# MA3050.net
KiCad netlist of a schematic drawn in EasyEDA Pro
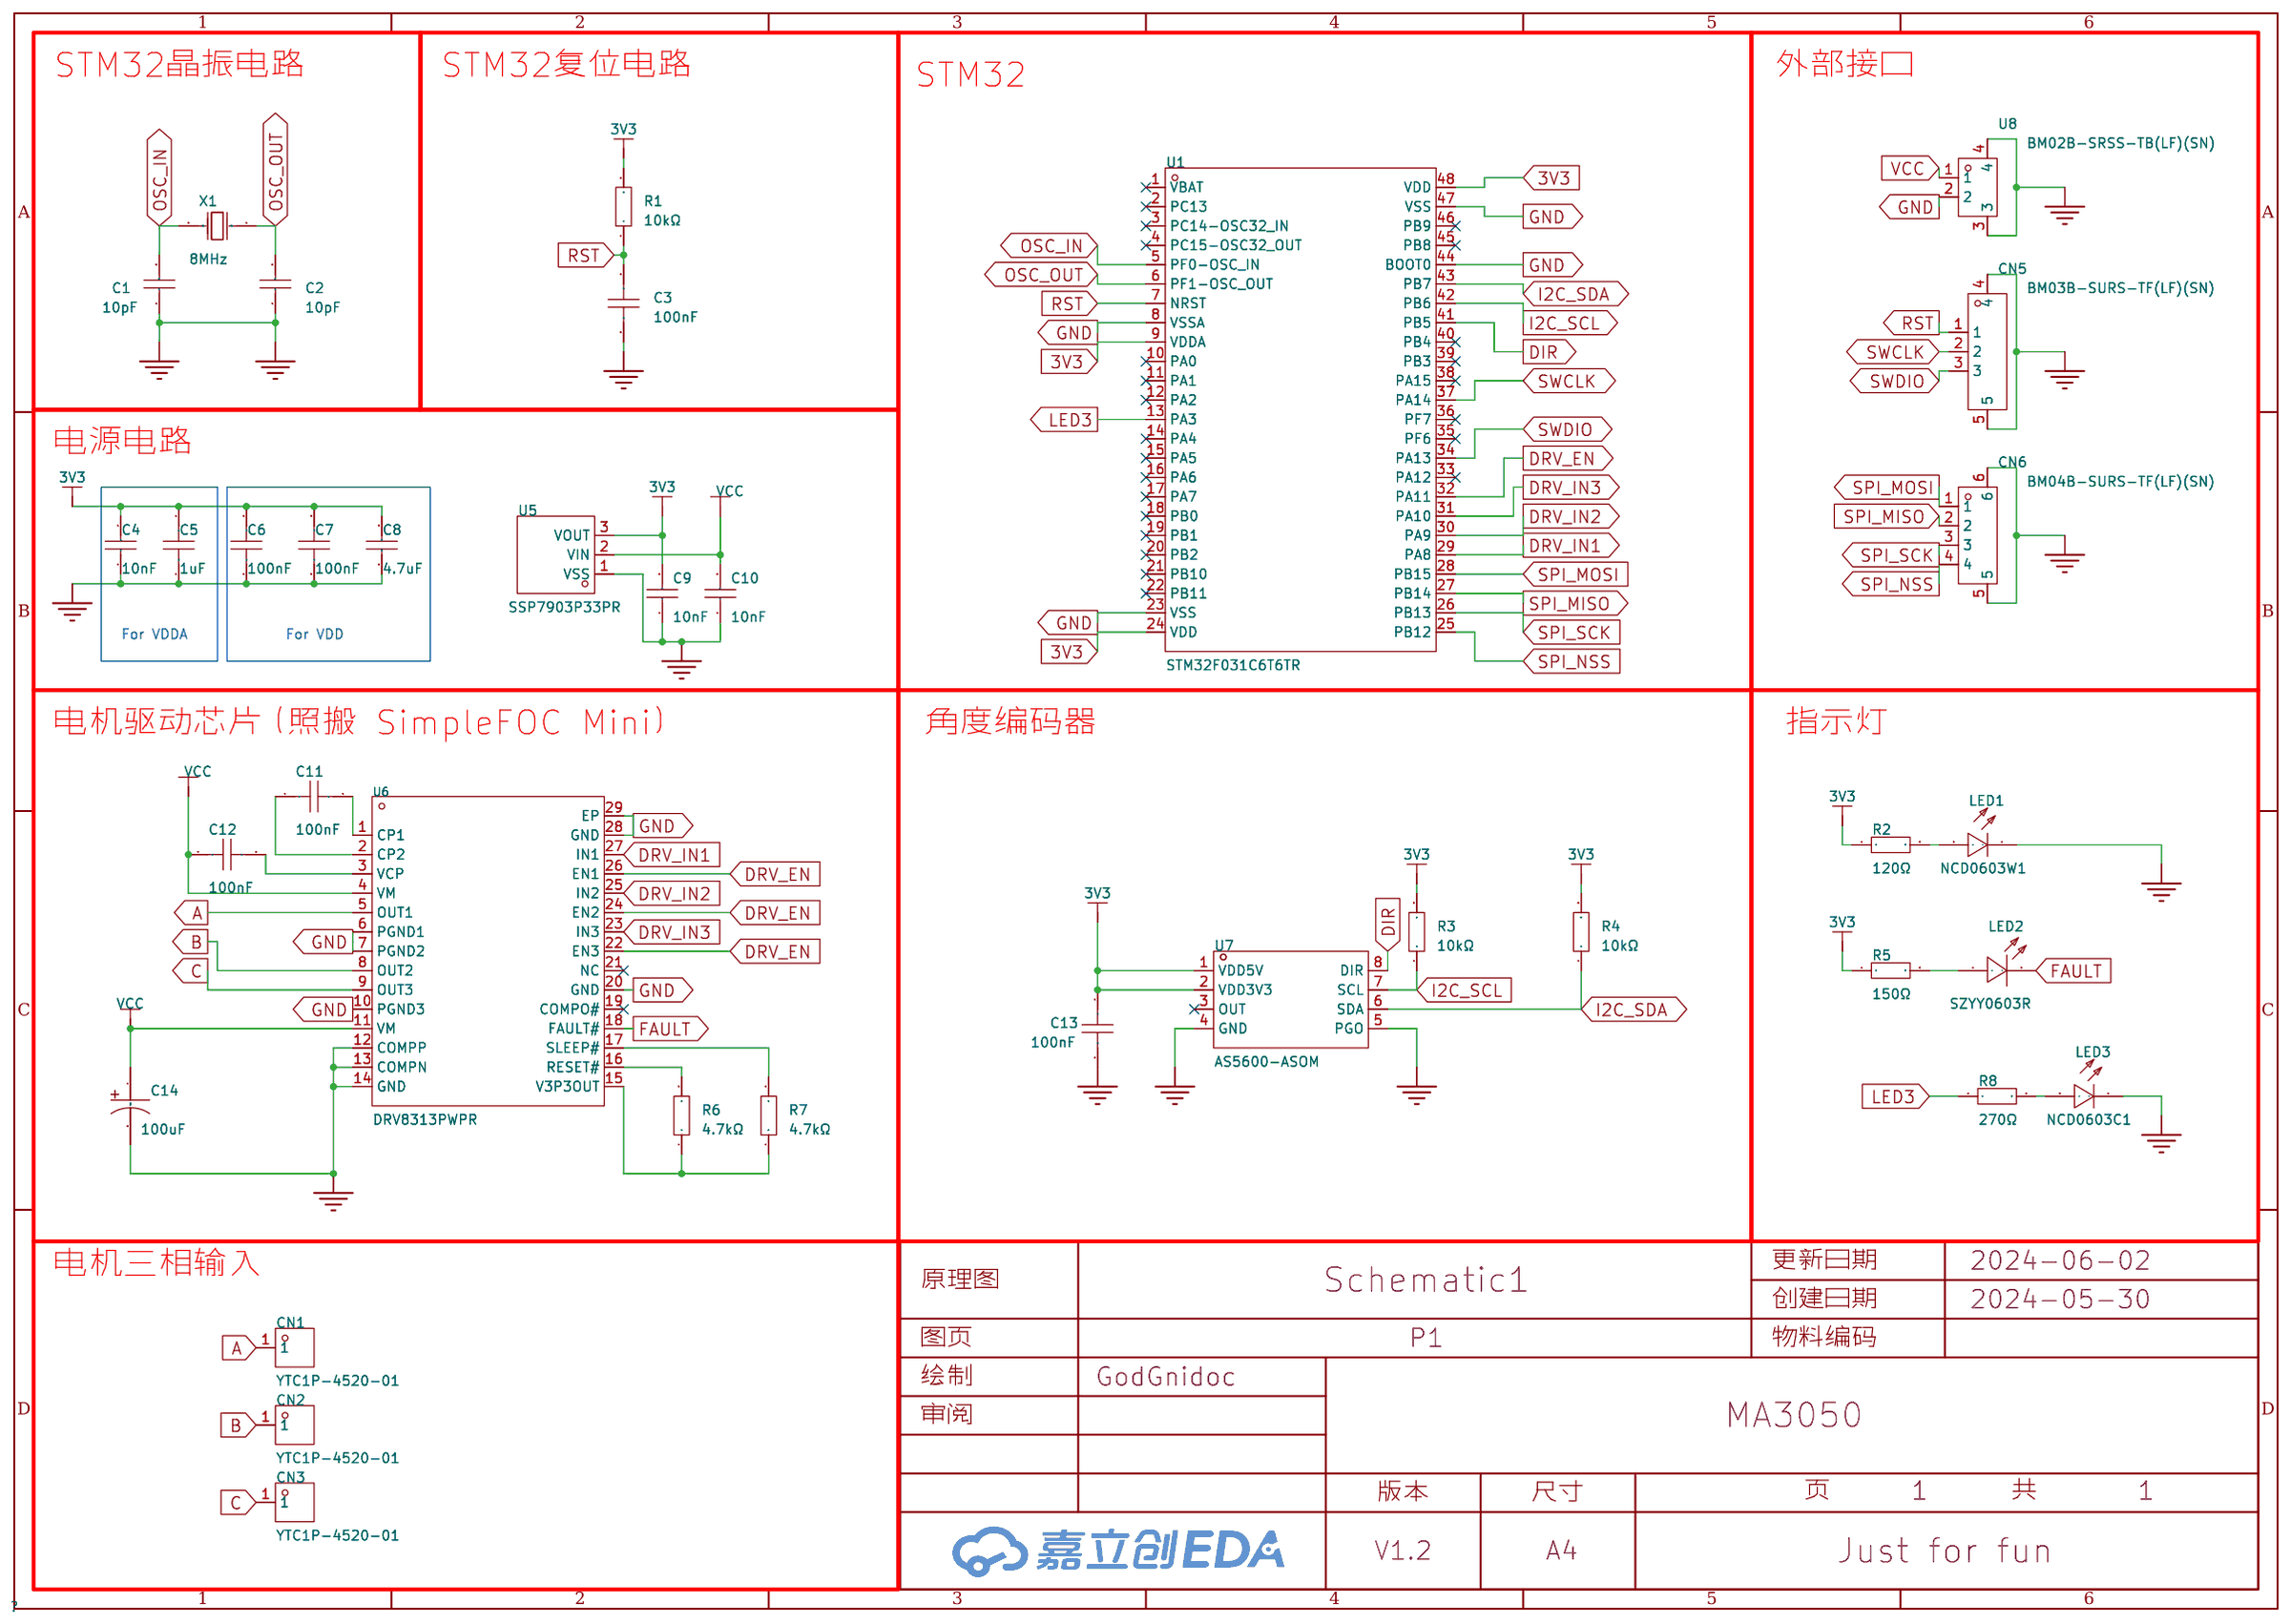
[diagram p0: schematic sheet]

(export (version "E")
  (design (tool "Eeschema 10.0.6"))
  (components
    (comp (ref "C1")
      (value "10pF")
      (footprint "easyedapro:C0603")
      (description "容值:10pF;精度:±5%;额定电压:50V;材质(温度系数):C0G;")
      (fields
        (field (name "Manufacturer Part") "CL10C100JB8NNNC")
        (field (name "Manufacturer") "SAMSUNG(三星)")
      )
      (libsource (lib "easyedapro") (part "CL10C100JB8NNNC"))
    )
    (comp (ref "C2")
      (value "10pF")
      (footprint "easyedapro:C0603")
      (description "容值:10pF;精度:±5%;额定电压:50V;材质(温度系数):C0G;")
      (fields
        (field (name "Manufacturer Part") "CL10C100JB8NNNC")
        (field (name "Manufacturer") "SAMSUNG(三星)")
      )
      (libsource (lib "easyedapro") (part "CL10C100JB8NNNC"))
    )
    (comp (ref "C3")
      (value "100nF")
      (footprint "easyedapro:C0603")
      (description "容值:100nF;精度:±10%;额定电压:50V;材质(温度系数):X7R;")
      (fields
        (field (name "Manufacturer Part") "CL10B104KB8NNNC")
        (field (name "Manufacturer") "SAMSUNG(三星)")
      )
      (libsource (lib "easyedapro") (part "CL10B104KB8NNNC"))
    )
    (comp (ref "C4")
      (value "10nF")
      (footprint "easyedapro:C0603")
      (description "容值:10nF;精度:±10%;额定电压:50V;材质(温度系数):X7R;")
      (fields
        (field (name "Manufacturer Part") "CC0603KRX7R9BB103")
        (field (name "Manufacturer") "YAGEO(国巨)")
      )
      (libsource (lib "easyedapro") (part "CC0603KRX7R9BB103"))
    )
    (comp (ref "C5")
      (value "1uF")
      (footprint "easyedapro:C0603")
      (description "容值:1uF;精度:±10%;额定电压:50V;材质(温度系数):X5R;")
      (fields
        (field (name "Manufacturer Part") "CL10A105KB8NNNC")
        (field (name "Manufacturer") "SAMSUNG(三星)")
      )
      (libsource (lib "easyedapro") (part "CL10A105KB8NNNC"))
    )
    (comp (ref "C6")
      (value "100nF")
      (footprint "easyedapro:C0603")
      (fields
        (field (name "Manufacturer Part") "CL10B104KB8NNNC")
        (field (name "Manufacturer") "SAMSUNG(三星)")
      )
      (libsource (lib "easyedapro") (part "CapAcitance"))
    )
    (comp (ref "C7")
      (value "100nF")
      (footprint "easyedapro:C0603")
      (fields
        (field (name "Manufacturer Part") "CL10B104KB8NNNC")
        (field (name "Manufacturer") "SAMSUNG(三星)")
      )
      (libsource (lib "easyedapro") (part "CapAcitance"))
    )
    (comp (ref "C8")
      (value "4.7uF")
      (footprint "easyedapro:C0603")
      (description "容值:4.7uF;精度:±10%;额定电压:16V;材质(温度系数):X5R;")
      (fields
        (field (name "Manufacturer Part") "CL10A475KO8NNNC")
        (field (name "Manufacturer") "SAMSUNG(三星)")
      )
      (libsource (lib "easyedapro") (part "CL10A475KO8NNNC"))
    )
    (comp (ref "C9")
      (value "10nF")
      (footprint "easyedapro:C0603")
      (description "容值:10nF;精度:±10%;额定电压:50V;材质(温度系数):X7R;")
      (fields
        (field (name "Manufacturer Part") "CC0603KRX7R9BB103")
        (field (name "Manufacturer") "YAGEO(国巨)")
      )
      (libsource (lib "easyedapro") (part "CC0603KRX7R9BB103"))
    )
    (comp (ref "C10")
      (value "10nF")
      (footprint "easyedapro:C0603")
      (description "容值:10nF;精度:±10%;额定电压:50V;材质(温度系数):X7R;")
      (fields
        (field (name "Manufacturer Part") "CC0603KRX7R9BB103")
        (field (name "Manufacturer") "YAGEO(国巨)")
      )
      (libsource (lib "easyedapro") (part "CC0603KRX7R9BB103"))
    )
    (comp (ref "C11")
      (value "100nF")
      (footprint "easyedapro:C0603")
      (fields
        (field (name "Manufacturer Part") "CL10B104KB8NNNC")
        (field (name "Manufacturer") "SAMSUNG(三星)")
      )
      (libsource (lib "easyedapro") (part "CapAcitance"))
    )
    (comp (ref "C12")
      (value "100nF")
      (footprint "easyedapro:C0603")
      (fields
        (field (name "Manufacturer Part") "CL10B104KB8NNNC")
        (field (name "Manufacturer") "SAMSUNG(三星)")
      )
      (libsource (lib "easyedapro") (part "CapAcitance"))
    )
    (comp (ref "C13")
      (value "100nF")
      (footprint "easyedapro:C0603")
      (fields
        (field (name "Manufacturer Part") "CL10B104KB8NNNC")
        (field (name "Manufacturer") "SAMSUNG(三星)")
      )
      (libsource (lib "easyedapro") (part "CapAcitance"))
    )
    (comp (ref "C14")
      (value "100uF")
      (footprint "easyedapro:CAP-SMD_BD6.3-L6.6-W6.6-FD")
      (description "容值:100uF;精度:±20%;额定电压:35V;纹波电流:-;等效串联电阻:-;")
      (fields (field (name "Manufacturer Part") "VT1V101M-CRE77") (field (name "Manufacturer") "VT(首科)"))
      (libsource (lib "easyedapro") (part "VT1V101M-CRE77"))
    )
    (comp (ref "CN1")
      (value "YTC1P-4520-01")
      (footprint "easyedapro:TESTPOINT-SMD_BD2.0_YTC1P-4520-01")
      (description "类型:弹簧顶针(POGO PIN);PIN位数:单PIN位;全长/全高:6.5mm;额定电流:2.5A;额定电压:12V;触头材质:黄铜;触头镀层:金;")
      (fields (field (name "Manufacturer") "YIYUAN(怡远)"))
      (libsource (lib "easyedapro") (part "YTC1P-4520-01"))
    )
    (comp (ref "CN2")
      (value "YTC1P-4520-01")
      (footprint "easyedapro:TESTPOINT-SMD_BD2.0_YTC1P-4520-01")
      (description "类型:弹簧顶针(POGO PIN);PIN位数:单PIN位;全长/全高:6.5mm;额定电流:2.5A;额定电压:12V;触头材质:黄铜;触头镀层:金;")
      (fields (field (name "Manufacturer") "YIYUAN(怡远)"))
      (libsource (lib "easyedapro") (part "YTC1P-4520-01"))
    )
    (comp (ref "CN3")
      (value "YTC1P-4520-01")
      (footprint "easyedapro:TESTPOINT-SMD_BD2.0_YTC1P-4520-01")
      (description "类型:弹簧顶针(POGO PIN);PIN位数:单PIN位;全长/全高:6.5mm;额定电流:2.5A;额定电压:12V;触头材质:黄铜;触头镀层:金;")
      (fields (field (name "Manufacturer") "YIYUAN(怡远)"))
      (libsource (lib "easyedapro") (part "YTC1P-4520-01"))
    )
    (comp (ref "CN5")
      (value "BM03B-SURS-TF(LF)(SN)")
      (footprint "easyedapro:CONN-SMD_BM03B-SURS-TF")
      (fields (field (name "Manufacturer") "JST"))
      (libsource (lib "easyedapro") (part "BM03B-SURS-TF(LF)(SN)"))
    )
    (comp (ref "CN6")
      (value "BM04B-SURS-TF(LF)(SN)")
      (footprint "easyedapro:CONN-SMD_BM04B-SURS-TF-LF-SN")
      (fields (field (name "Manufacturer") "JST"))
      (libsource (lib "easyedapro") (part "BM04B-SURS-TF(LF)(SN)"))
    )
    (comp (ref "LED1")
      (value "NCD0603W1")
      (footprint "easyedapro:LED0603-RD")
      (fields (field (name "Manufacturer") "国星光电"))
      (libsource (lib "easyedapro") (part "FC-D1608WD-460H5"))
    )
    (comp (ref "LED2")
      (value "SZYY0603R")
      (footprint "easyedapro:LED0603-R-RD")
      (fields (field (name "Manufacturer") "yongyu(永裕光电)"))
      (libsource (lib "easyedapro") (part "SZYY0603R"))
    )
    (comp (ref "LED3")
      (value "NCD0603C1")
      (footprint "easyedapro:LED0603-RD")
      (fields (field (name "Manufacturer") "国星光电"))
      (libsource (lib "easyedapro") (part "FC-D1608HGK-572C"))
    )
    (comp (ref "R1")
      (value "10kΩ")
      (footprint "easyedapro:R0603")
      (description "电阻类型:厚膜电阻;阻值:10kΩ;精度:±1%;功率:100mW;最大工作电压:75V;温度系数:±100ppm/°C;")
      (fields
        (field (name "Manufacturer Part") "0603WAF1002T5E")
        (field (name "Manufacturer") "UNI-ROYAL(厚声)")
      )
      (libsource (lib "easyedapro") (part "0603WAF1002T5E"))
    )
    (comp (ref "R2")
      (value "120Ω")
      (footprint "easyedapro:R0603")
      (description "电阻类型:厚膜电阻;阻值:120Ω;精度:±1%;功率:100mW;最大工作电压:75V;温度系数:±100ppm/°C;")
      (fields
        (field (name "Manufacturer Part") "0603WAF1200T5E")
        (field (name "Manufacturer") "UNI-ROYAL(厚声)")
      )
      (libsource (lib "easyedapro") (part "0603WAF1200T5E"))
    )
    (comp (ref "R3")
      (value "10kΩ")
      (footprint "easyedapro:R0603")
      (description "电阻类型:厚膜电阻;阻值:10kΩ;精度:±1%;功率:100mW;最大工作电压:75V;温度系数:±100ppm/°C;")
      (fields
        (field (name "Manufacturer Part") "0603WAF1002T5E")
        (field (name "Manufacturer") "UNI-ROYAL(厚声)")
      )
      (libsource (lib "easyedapro") (part "0603WAF1002T5E"))
    )
    (comp (ref "R4")
      (value "10kΩ")
      (footprint "easyedapro:R0603")
      (description "电阻类型:厚膜电阻;阻值:10kΩ;精度:±1%;功率:100mW;最大工作电压:75V;温度系数:±100ppm/°C;")
      (fields
        (field (name "Manufacturer Part") "0603WAF1002T5E")
        (field (name "Manufacturer") "UNI-ROYAL(厚声)")
      )
      (libsource (lib "easyedapro") (part "0603WAF1002T5E"))
    )
    (comp (ref "R5")
      (value "150Ω")
      (footprint "easyedapro:R0603")
      (description "电阻类型:厚膜电阻;阻值:150Ω;精度:±1%;功率:100mW;最大工作电压:75V;温度系数:±100ppm/°C;")
      (fields
        (field (name "Manufacturer Part") "0603WAF1500T5E")
        (field (name "Manufacturer") "UNI-ROYAL(厚声)")
      )
      (libsource (lib "easyedapro") (part "0603WAF1500T5E"))
    )
    (comp (ref "R6")
      (value "4.7kΩ")
      (footprint "easyedapro:R0603")
      (description "电阻类型:厚膜电阻;阻值:4.7kΩ;精度:±1%;功率:100mW;最大工作电压:75V;温度系数:±100ppm/°C;")
      (fields
        (field (name "Manufacturer Part") "0603WAF4701T5E")
        (field (name "Manufacturer") "UNI-ROYAL(厚声)")
      )
      (libsource (lib "easyedapro") (part "0603WAF4701T5E"))
    )
    (comp (ref "R7")
      (value "4.7kΩ")
      (footprint "easyedapro:R0603")
      (description "电阻类型:厚膜电阻;阻值:4.7kΩ;精度:±1%;功率:100mW;最大工作电压:75V;温度系数:±100ppm/°C;")
      (fields
        (field (name "Manufacturer Part") "0603WAF4701T5E")
        (field (name "Manufacturer") "UNI-ROYAL(厚声)")
      )
      (libsource (lib "easyedapro") (part "0603WAF4701T5E"))
    )
    (comp (ref "R8")
      (value "270Ω")
      (footprint "easyedapro:R0603")
      (description "电阻类型:厚膜电阻;阻值:270Ω;精度:±1%;功率:100mW;最大工作电压:75V;温度系数:±100ppm/°C;")
      (fields
        (field (name "Manufacturer Part") "0603WAF2700T5E")
        (field (name "Manufacturer") "UNI-ROYAL(厚声)")
      )
      (libsource (lib "easyedapro") (part "0603WAF2700T5E"))
    )
    (comp (ref "U1")
      (value "STM32F031C6T6TR")
      (footprint "easyedapro:LQFP-48_L7.0-W7.0-P0.50-LS9.0-TL")
      (description "CPU内核:CM0;程序存储容量:32KB;RAM总容量:4KB;GPIO端口数量:39;工作电压范围:2V~3.6V;CPU最大主频:48MHz;程序存储器类型:FLASH;")
      (fields (field (name "Manufacturer") "ST(意法半导体)"))
      (libsource (lib "easyedapro") (part "STM32F031C6T6TR"))
    )
    (comp (ref "U5")
      (value "SSP7903P33PR")
      (footprint "easyedapro:SOT-89-3_L4.5-W2.5-P1.50-LS4.1-BR")
      (description "最大输入电压:40V;输出电压:3.3V;最大输出电流:1A;电源纹波抑制比(PSRR):73.2dB@(10Hz);输出极性:正极;")
      (fields (field (name "Manufacturer") "Siproin(上海矽朋)"))
      (libsource (lib "easyedapro") (part "SSP7903P33PR"))
    )
    (comp (ref "U6")
      (value "DRV8313PWPR")
      (footprint "easyedapro:HTSSOP-28_L9.8-W4.5-P0.65-LS6.6-BL-EP")
      (description "驱动电机类型:无刷直流BLDC;电源电压:8V~60V;输出电流:-;接口:并行;")
      (fields (field (name "Manufacturer") "TI(德州仪器)"))
      (libsource (lib "easyedapro") (part "DRV8313PWPR"))
    )
    (comp (ref "U7")
      (value "AS5600-ASOM")
      (footprint "easyedapro:SOIC-8_L5.0-W4.0-P1.27-LS6.0-BL")
      (description "旋转角度范围:0°~360°;")
      (fields (field (name "Manufacturer") "ams(艾迈斯半导体)"))
      (libsource (lib "easyedapro") (part "AS5600-ASOM"))
    )
    (comp (ref "U8")
      (value "BM02B-SRSS-TB(LF)(SN)")
      (footprint "easyedapro:CONN-SMD_2P-P2.50_HCTL_HC-XH-2ALT")
      (fields (field (name "Manufacturer") "JST"))
      (libsource (lib "easyedapro") (part "ZX-XH2.54-2PLT"))
    )
    (comp (ref "X1")
      (value "8MHz")
      (footprint "easyedapro:CRYSTAL-SMD_L5.0-W3.2")
      (description "晶振类型:贴片晶振;频率:8MHz;常温频差:±10ppm;外接负载电容:20pF;频率稳定度(全温):±20ppm;")
      (fields (field (name "Manufacturer Part") "X50328MSB2GI") (field (name "Manufacturer") "YXC(扬兴晶振)"))
      (libsource (lib "easyedapro") (part "X50328MSB2GI"))
    )
  )
  (nets
    (net (code "1") (name "3V3") (class "Default")
      (node (ref "C13") (pin "1") (pinfunction "1_1") (pintype "input"))
      (node (ref "C4") (pin "2") (pinfunction "2_2") (pintype "input"))
      (node (ref "C5") (pin "2") (pinfunction "2_2") (pintype "unspecified"))
      (node (ref "C6") (pin "2") (pinfunction "2_2") (pintype "input"))
      (node (ref "C7") (pin "2") (pinfunction "2_2") (pintype "input"))
      (node (ref "C8") (pin "2") (pinfunction "2_2") (pintype "input"))
      (node (ref "C9") (pin "2") (pinfunction "2_2") (pintype "input"))
      (node (ref "R1") (pin "2") (pinfunction "2_2") (pintype "input"))
      (node (ref "R2") (pin "1") (pinfunction "1_1") (pintype "input"))
      (node (ref "R3") (pin "2") (pinfunction "2_2") (pintype "input"))
      (node (ref "R4") (pin "2") (pinfunction "2_2") (pintype "input"))
      (node (ref "R5") (pin "1") (pinfunction "1_1") (pintype "input"))
      (node (ref "U1") (pin "24") (pinfunction "VDD_24") (pintype "input"))
      (node (ref "U1") (pin "48") (pinfunction "VDD_48") (pintype "input"))
      (node (ref "U1") (pin "9") (pinfunction "VDDA_9") (pintype "input"))
      (node (ref "U5") (pin "3") (pinfunction "VOUT_3") (pintype "unspecified"))
      (node (ref "U7") (pin "1") (pinfunction "VDD5V_1") (pintype "input"))
      (node (ref "U7") (pin "2") (pinfunction "VDD3V3_2") (pintype "input"))
    )
    (net (code "2") (name "A") (class "Default")
      (node (ref "CN1") (pin "1") (pinfunction "1_1") (pintype "unspecified"))
      (node (ref "U6") (pin "5") (pinfunction "OUT1_5") (pintype "input"))
    )
    (net (code "3") (name "B") (class "Default")
      (node (ref "CN2") (pin "1") (pinfunction "1_1") (pintype "unspecified"))
      (node (ref "U6") (pin "8") (pinfunction "OUT2_8") (pintype "input"))
    )
    (net (code "4") (name "C") (class "Default")
      (node (ref "CN3") (pin "1") (pinfunction "1_1") (pintype "unspecified"))
      (node (ref "U6") (pin "9") (pinfunction "OUT3_9") (pintype "input"))
    )
    (net (code "5") (name "DIR") (class "Default")
      (node (ref "U1") (pin "41") (pinfunction "PB5_41") (pintype "input"))
      (node (ref "U7") (pin "8") (pinfunction "DIR_8") (pintype "input"))
    )
    (net (code "6") (name "DRV_EN") (class "Default")
      (node (ref "U1") (pin "32") (pinfunction "PA11_32") (pintype "input"))
      (node (ref "U6") (pin "22") (pinfunction "EN3_22") (pintype "input"))
      (node (ref "U6") (pin "24") (pinfunction "EN2_24") (pintype "input"))
      (node (ref "U6") (pin "26") (pinfunction "EN1_26") (pintype "input"))
    )
    (net (code "7") (name "DRV_IN1") (class "Default")
      (node (ref "U1") (pin "29") (pinfunction "PA8_29") (pintype "input"))
      (node (ref "U6") (pin "27") (pinfunction "IN1_27") (pintype "input"))
    )
    (net (code "8") (name "DRV_IN2") (class "Default")
      (node (ref "U1") (pin "30") (pinfunction "PA9_30") (pintype "input"))
      (node (ref "U6") (pin "25") (pinfunction "IN2_25") (pintype "input"))
    )
    (net (code "9") (name "DRV_IN3") (class "Default")
      (node (ref "U1") (pin "31") (pinfunction "PA10_31") (pintype "input"))
      (node (ref "U6") (pin "23") (pinfunction "IN3_23") (pintype "input"))
    )
    (net (code "10") (name "FAULT") (class "Default")
      (node (ref "LED2") (pin "2") (pinfunction "-_2") (pintype "unspecified"))
      (node (ref "U6") (pin "18") (pinfunction "FAULT#_18") (pintype "input"))
    )
    (net (code "11") (name "GND") (class "Default")
      (node (ref "C1") (pin "1") (pinfunction "1_1") (pintype "input"))
      (node (ref "C10") (pin "1") (pinfunction "1_1") (pintype "input"))
      (node (ref "C13") (pin "2") (pinfunction "2_2") (pintype "input"))
      (node (ref "C14") (pin "2") (pinfunction "2_2") (pintype "unspecified"))
      (node (ref "C2") (pin "1") (pinfunction "1_1") (pintype "input"))
      (node (ref "C3") (pin "1") (pinfunction "1_1") (pintype "unspecified"))
      (node (ref "C4") (pin "1") (pinfunction "1_1") (pintype "input"))
      (node (ref "C5") (pin "1") (pinfunction "1_1") (pintype "unspecified"))
      (node (ref "C6") (pin "1") (pinfunction "1_1") (pintype "input"))
      (node (ref "C7") (pin "1") (pinfunction "1_1") (pintype "input"))
      (node (ref "C8") (pin "1") (pinfunction "1_1") (pintype "input"))
      (node (ref "C9") (pin "1") (pinfunction "1_1") (pintype "input"))
      (node (ref "CN5") (pin "4") (pinfunction "4_4") (pintype "unspecified"))
      (node (ref "CN5") (pin "5") (pinfunction "5_5") (pintype "unspecified"))
      (node (ref "CN6") (pin "5") (pinfunction "5_5") (pintype "unspecified"))
      (node (ref "CN6") (pin "6") (pinfunction "6_6") (pintype "unspecified"))
      (node (ref "LED1") (pin "1") (pinfunction "-_1") (pintype "input"))
      (node (ref "LED3") (pin "1") (pinfunction "-_1") (pintype "input"))
      (node (ref "U1") (pin "23") (pinfunction "VSS_23") (pintype "input"))
      (node (ref "U1") (pin "44") (pinfunction "BOOT0_44") (pintype "input"))
      (node (ref "U1") (pin "47") (pinfunction "VSS_47") (pintype "input"))
      (node (ref "U1") (pin "8") (pinfunction "VSSA_8") (pintype "input"))
      (node (ref "U5") (pin "1") (pinfunction "VSS_1") (pintype "unspecified"))
      (node (ref "U6") (pin "10") (pinfunction "PGND3_10") (pintype "input"))
      (node (ref "U6") (pin "12") (pinfunction "COMPP_12") (pintype "input"))
      (node (ref "U6") (pin "13") (pinfunction "COMPN_13") (pintype "input"))
      (node (ref "U6") (pin "14") (pinfunction "GND_14") (pintype "input"))
      (node (ref "U6") (pin "20") (pinfunction "GND_20") (pintype "input"))
      (node (ref "U6") (pin "28") (pinfunction "GND_28") (pintype "input"))
      (node (ref "U6") (pin "29") (pinfunction "EP_29") (pintype "input"))
      (node (ref "U6") (pin "6") (pinfunction "PGND1_6") (pintype "input"))
      (node (ref "U6") (pin "7") (pinfunction "PGND2_7") (pintype "input"))
      (node (ref "U7") (pin "4") (pinfunction "GND_4") (pintype "input"))
      (node (ref "U7") (pin "5") (pinfunction "PGO_5") (pintype "input"))
      (node (ref "U8") (pin "2") (pinfunction "2_2") (pintype "unspecified"))
      (node (ref "U8") (pin "3") (pinfunction "3_3") (pintype "unspecified"))
      (node (ref "U8") (pin "4") (pinfunction "4_4") (pintype "unspecified"))
    )
    (net (code "12") (name "I2C_SCL") (class "Default")
      (node (ref "R3") (pin "1") (pinfunction "1_1") (pintype "input"))
      (node (ref "U1") (pin "42") (pinfunction "PB6_42") (pintype "input"))
      (node (ref "U7") (pin "7") (pinfunction "SCL_7") (pintype "input"))
    )
    (net (code "13") (name "I2C_SDA") (class "Default")
      (node (ref "R4") (pin "1") (pinfunction "1_1") (pintype "input"))
      (node (ref "U1") (pin "43") (pinfunction "PB7_43") (pintype "input"))
      (node (ref "U7") (pin "6") (pinfunction "SDA_6") (pintype "input"))
    )
    (net (code "14") (name "LED3") (class "Default")
      (node (ref "R8") (pin "1") (pinfunction "1_1") (pintype "input"))
      (node (ref "U1") (pin "13") (pinfunction "PA3_13") (pintype "input"))
    )
    (net (code "15") (name "Net-(LED1-+)") (class "Default")
      (node (ref "LED1") (pin "2") (pinfunction "+_2") (pintype "input"))
      (node (ref "R2") (pin "2") (pinfunction "2_2") (pintype "input"))
    )
    (net (code "16") (name "Net-(LED2-+)") (class "Default")
      (node (ref "LED2") (pin "1") (pinfunction "+_1") (pintype "unspecified"))
      (node (ref "R5") (pin "2") (pinfunction "2_2") (pintype "input"))
    )
    (net (code "17") (name "Net-(LED3-+)") (class "Default")
      (node (ref "LED3") (pin "2") (pinfunction "+_2") (pintype "input"))
      (node (ref "R8") (pin "2") (pinfunction "2_2") (pintype "input"))
    )
    (net (code "18") (name "Net-(U6-CP1)") (class "Default")
      (node (ref "C11") (pin "2") (pinfunction "2_2") (pintype "input"))
      (node (ref "U6") (pin "1") (pinfunction "CP1_1") (pintype "input"))
    )
    (net (code "19") (name "Net-(U6-CP2)") (class "Default")
      (node (ref "C11") (pin "1") (pinfunction "1_1") (pintype "input"))
      (node (ref "U6") (pin "2") (pinfunction "CP2_2") (pintype "input"))
    )
    (net (code "20") (name "Net-(U6-RESET#)") (class "Default")
      (node (ref "R6") (pin "2") (pinfunction "2_2") (pintype "input"))
      (node (ref "U6") (pin "16") (pinfunction "RESET#_16") (pintype "input"))
    )
    (net (code "21") (name "Net-(U6-SLEEP#)") (class "Default")
      (node (ref "R7") (pin "2") (pinfunction "2_2") (pintype "input"))
      (node (ref "U6") (pin "17") (pinfunction "SLEEP#_17") (pintype "input"))
    )
    (net (code "22") (name "Net-(U6-V3P3OUT)") (class "Default")
      (node (ref "R6") (pin "1") (pinfunction "1_1") (pintype "input"))
      (node (ref "R7") (pin "1") (pinfunction "1_1") (pintype "input"))
      (node (ref "U6") (pin "15") (pinfunction "V3P3OUT_15") (pintype "input"))
    )
    (net (code "23") (name "Net-(U6-VCP)") (class "Default")
      (node (ref "C12") (pin "2") (pinfunction "2_2") (pintype "input"))
      (node (ref "U6") (pin "3") (pinfunction "VCP_3") (pintype "input"))
    )
    (net (code "24") (name "OSC_IN") (class "Default")
      (node (ref "C1") (pin "2") (pinfunction "2_2") (pintype "input"))
      (node (ref "U1") (pin "5") (pinfunction "PF0-OSC_IN_5") (pintype "input"))
      (node (ref "X1") (pin "2") (pinfunction "OSC2_2") (pintype "input"))
    )
    (net (code "25") (name "OSC_OUT") (class "Default")
      (node (ref "C2") (pin "2") (pinfunction "2_2") (pintype "input"))
      (node (ref "U1") (pin "6") (pinfunction "PF1-OSC_OUT_6") (pintype "input"))
      (node (ref "X1") (pin "1") (pinfunction "OSC1_1") (pintype "input"))
    )
    (net (code "26") (name "RST") (class "Default")
      (node (ref "C3") (pin "2") (pinfunction "2_2") (pintype "unspecified"))
      (node (ref "CN5") (pin "1") (pinfunction "1_1") (pintype "unspecified"))
      (node (ref "R1") (pin "1") (pinfunction "1_1") (pintype "input"))
      (node (ref "U1") (pin "7") (pinfunction "NRST_7") (pintype "input"))
    )
    (net (code "27") (name "SPI_MISO") (class "Default")
      (node (ref "CN6") (pin "2") (pinfunction "2_2") (pintype "unspecified"))
      (node (ref "U1") (pin "27") (pinfunction "PB14_27") (pintype "input"))
    )
    (net (code "28") (name "SPI_MOSI") (class "Default")
      (node (ref "CN6") (pin "1") (pinfunction "1_1") (pintype "unspecified"))
      (node (ref "U1") (pin "28") (pinfunction "PB15_28") (pintype "input"))
    )
    (net (code "29") (name "SPI_NSS") (class "Default")
      (node (ref "CN6") (pin "4") (pinfunction "4_4") (pintype "unspecified"))
      (node (ref "U1") (pin "25") (pinfunction "PB12_25") (pintype "input"))
    )
    (net (code "30") (name "SPI_SCK") (class "Default")
      (node (ref "CN6") (pin "3") (pinfunction "3_3") (pintype "unspecified"))
      (node (ref "U1") (pin "26") (pinfunction "PB13_26") (pintype "input"))
    )
    (net (code "31") (name "SWCLK") (class "Default")
      (node (ref "CN5") (pin "2") (pinfunction "2_2") (pintype "unspecified"))
      (node (ref "U1") (pin "37") (pinfunction "PA14_37") (pintype "input"))
    )
    (net (code "32") (name "SWDIO") (class "Default")
      (node (ref "CN5") (pin "3") (pinfunction "3_3") (pintype "unspecified"))
      (node (ref "U1") (pin "34") (pinfunction "PA13_34") (pintype "input"))
    )
    (net (code "33") (name "VCC") (class "Default")
      (node (ref "C10") (pin "2") (pinfunction "2_2") (pintype "input"))
      (node (ref "C12") (pin "1") (pinfunction "1_1") (pintype "input"))
      (node (ref "C14") (pin "1") (pinfunction "1_1") (pintype "unspecified"))
      (node (ref "U5") (pin "2") (pinfunction "VIN_2") (pintype "unspecified"))
      (node (ref "U6") (pin "11") (pinfunction "VM_11") (pintype "input"))
      (node (ref "U6") (pin "4") (pinfunction "VM_4") (pintype "input"))
      (node (ref "U8") (pin "1") (pinfunction "1_1") (pintype "unspecified"))
    )
    (net (code "34") (name "unconnected-(U1-PA0-Pad10)") (class "Default")
      (node (ref "U1") (pin "10") (pinfunction "PA0_10") (pintype "input+no_connect"))
    )
    (net (code "35") (name "unconnected-(U1-PA1-Pad11)") (class "Default")
      (node (ref "U1") (pin "11") (pinfunction "PA1_11") (pintype "input+no_connect"))
    )
    (net (code "36") (name "unconnected-(U1-PA2-Pad12)") (class "Default")
      (node (ref "U1") (pin "12") (pinfunction "PA2_12") (pintype "input+no_connect"))
    )
    (net (code "37") (name "unconnected-(U1-PA4-Pad14)") (class "Default")
      (node (ref "U1") (pin "14") (pinfunction "PA4_14") (pintype "input+no_connect"))
    )
    (net (code "38") (name "unconnected-(U1-PA5-Pad15)") (class "Default")
      (node (ref "U1") (pin "15") (pinfunction "PA5_15") (pintype "input+no_connect"))
    )
    (net (code "39") (name "unconnected-(U1-PA6-Pad16)") (class "Default")
      (node (ref "U1") (pin "16") (pinfunction "PA6_16") (pintype "input+no_connect"))
    )
    (net (code "40") (name "unconnected-(U1-PA7-Pad17)") (class "Default")
      (node (ref "U1") (pin "17") (pinfunction "PA7_17") (pintype "input+no_connect"))
    )
    (net (code "41") (name "unconnected-(U1-PA12-Pad33)") (class "Default")
      (node (ref "U1") (pin "33") (pinfunction "PA12_33") (pintype "input+no_connect"))
    )
    (net (code "42") (name "unconnected-(U1-PA15-Pad38)") (class "Default")
      (node (ref "U1") (pin "38") (pinfunction "PA15_38") (pintype "input+no_connect"))
    )
    (net (code "43") (name "unconnected-(U1-PB0-Pad18)") (class "Default")
      (node (ref "U1") (pin "18") (pinfunction "PB0_18") (pintype "input+no_connect"))
    )
    (net (code "44") (name "unconnected-(U1-PB1-Pad19)") (class "Default")
      (node (ref "U1") (pin "19") (pinfunction "PB1_19") (pintype "input+no_connect"))
    )
    (net (code "45") (name "unconnected-(U1-PB2-Pad20)") (class "Default")
      (node (ref "U1") (pin "20") (pinfunction "PB2_20") (pintype "input+no_connect"))
    )
    (net (code "46") (name "unconnected-(U1-PB3-Pad39)") (class "Default")
      (node (ref "U1") (pin "39") (pinfunction "PB3_39") (pintype "input+no_connect"))
    )
    (net (code "47") (name "unconnected-(U1-PB4-Pad40)") (class "Default")
      (node (ref "U1") (pin "40") (pinfunction "PB4_40") (pintype "input+no_connect"))
    )
    (net (code "48") (name "unconnected-(U1-PB8-Pad45)") (class "Default")
      (node (ref "U1") (pin "45") (pinfunction "PB8_45") (pintype "input+no_connect"))
    )
    (net (code "49") (name "unconnected-(U1-PB9-Pad46)") (class "Default")
      (node (ref "U1") (pin "46") (pinfunction "PB9_46") (pintype "input+no_connect"))
    )
    (net (code "50") (name "unconnected-(U1-PB10-Pad21)") (class "Default")
      (node (ref "U1") (pin "21") (pinfunction "PB10_21") (pintype "input+no_connect"))
    )
    (net (code "51") (name "unconnected-(U1-PB11-Pad22)") (class "Default")
      (node (ref "U1") (pin "22") (pinfunction "PB11_22") (pintype "input+no_connect"))
    )
    (net (code "52") (name "unconnected-(U1-PC13-Pad2)") (class "Default")
      (node (ref "U1") (pin "2") (pinfunction "PC13_2") (pintype "input+no_connect"))
    )
    (net (code "53") (name "unconnected-(U1-PC14-OSC32_IN-Pad3)") (class "Default")
      (node (ref "U1") (pin "3") (pinfunction "PC14-OSC32_IN_3") (pintype "input+no_connect"))
    )
    (net (code "54") (name "unconnected-(U1-PC15-OSC32_OUT-Pad4)") (class "Default")
      (node (ref "U1") (pin "4") (pinfunction "PC15-OSC32_OUT_4") (pintype "input+no_connect"))
    )
    (net (code "55") (name "unconnected-(U1-PF6-Pad35)") (class "Default")
      (node (ref "U1") (pin "35") (pinfunction "PF6_35") (pintype "input+no_connect"))
    )
    (net (code "56") (name "unconnected-(U1-PF7-Pad36)") (class "Default")
      (node (ref "U1") (pin "36") (pinfunction "PF7_36") (pintype "input+no_connect"))
    )
    (net (code "57") (name "unconnected-(U1-VBAT-Pad1)") (class "Default")
      (node (ref "U1") (pin "1") (pinfunction "VBAT_1") (pintype "input+no_connect"))
    )
    (net (code "58") (name "unconnected-(U6-COMPO#-Pad19)") (class "Default")
      (node (ref "U6") (pin "19") (pinfunction "COMPO#_19") (pintype "input+no_connect"))
    )
    (net (code "59") (name "unconnected-(U6-NC-Pad21)") (class "Default")
      (node (ref "U6") (pin "21") (pinfunction "NC_21") (pintype "input+no_connect"))
    )
    (net (code "60") (name "unconnected-(U7-OUT-Pad3)") (class "Default")
      (node (ref "U7") (pin "3") (pinfunction "OUT_3") (pintype "input+no_connect"))
    )
  )
)
